# Supply.net
KiCad netlist of a schematic drawn in Altium Designer
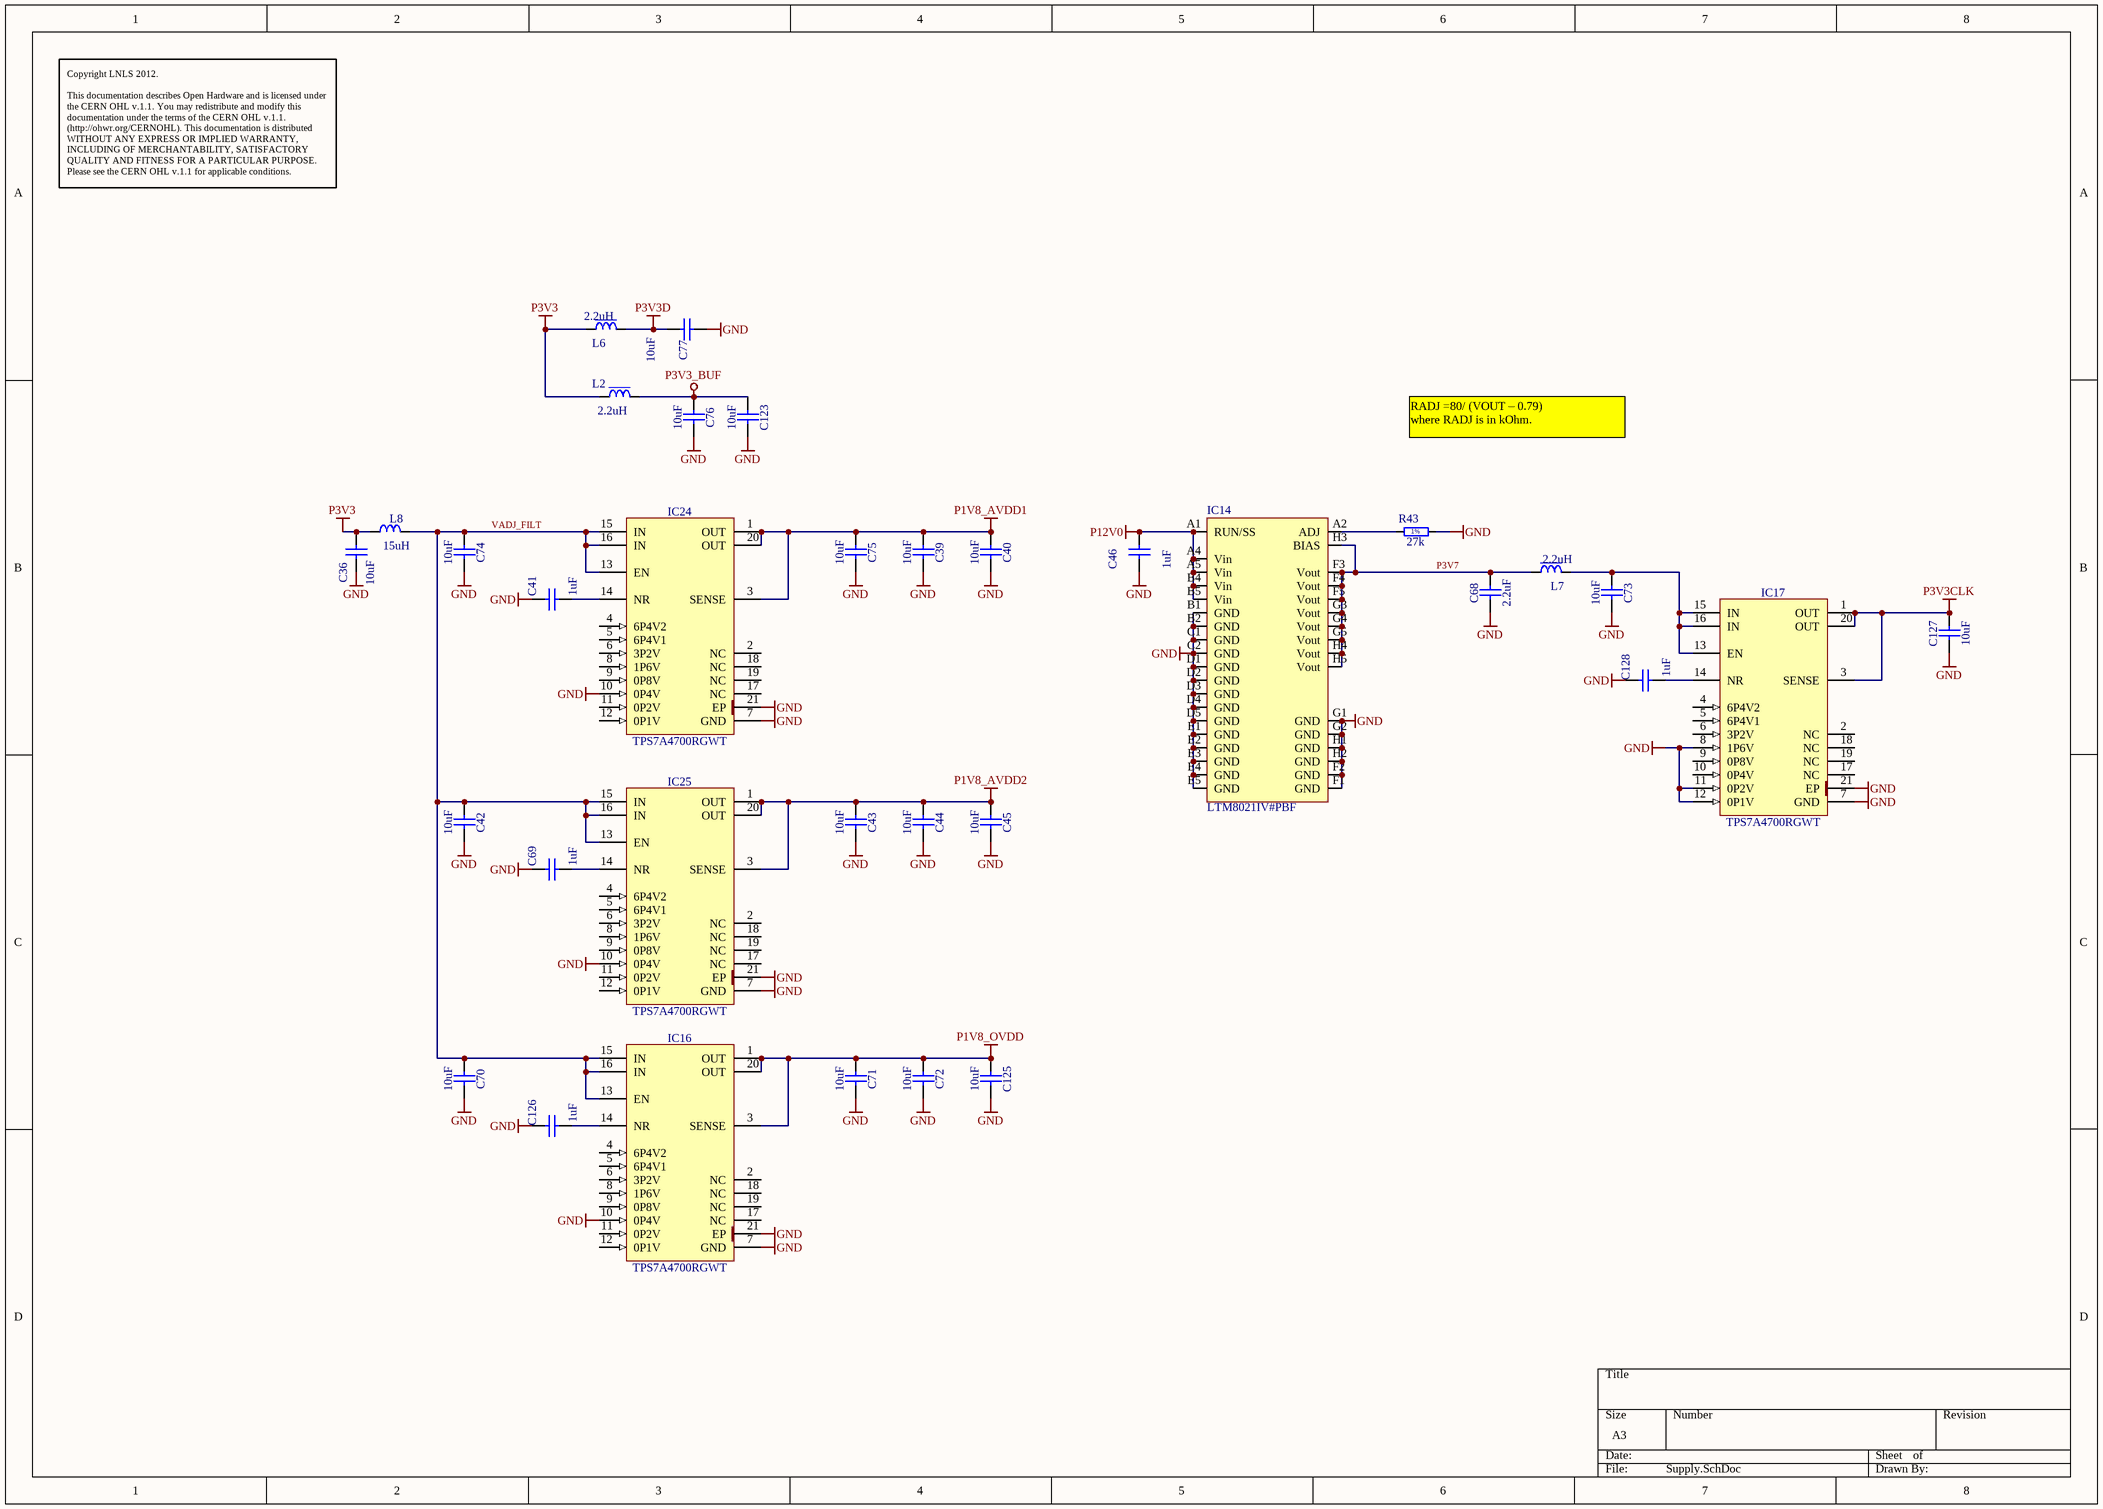
[diagram p0: Supply.SchDoc]

(export (version "E")
  (design (tool "Eeschema 10.0.6"))
  (components
    (comp (ref "C36")
      (value "10uF")
      (footprint "CAPC2012X135N")
      (description "Non-polarised capacitor")
      (fields
        (field (name "PART NUMBER") "CC0805_10UF_16V_10%_X5R")
        (field (name "VOLTAGE") "16V")
        (field (name "AUTHOR") "CERN DEM JLC")
      )
      (libsource (lib "Capacitors") (part "Capacitor - non polarized"))
    )
    (comp (ref "C39")
      (value "10uF")
      (footprint "CAPC2012X135N")
      (description "Non-polarised capacitor")
      (fields
        (field (name "PART NUMBER") "CC0805_10UF_16V_10%_X5R")
        (field (name "VOLTAGE") "16V")
        (field (name "AUTHOR") "CERN DEM JLC")
      )
      (libsource (lib "Capacitors") (part "Capacitor - non polarized"))
    )
    (comp (ref "C40")
      (value "10uF")
      (footprint "CAPC2012X135N")
      (description "Non-polarised capacitor")
      (fields
        (field (name "PART NUMBER") "CC0805_10UF_16V_10%_X5R")
        (field (name "VOLTAGE") "16V")
        (field (name "AUTHOR") "CERN DEM JLC")
      )
      (libsource (lib "Capacitors") (part "Capacitor - non polarized"))
    )
    (comp (ref "C41")
      (value "1uF")
      (footprint "CAPC1608X87N")
      (description "Non-polarised capacitor")
      (fields
        (field (name "PART NUMBER") "CC0603_1UF_16V_10%_X7R")
        (field (name "VOLTAGE") "16V")
        (field (name "AUTHOR") "CERN DEM JLC")
      )
      (libsource (lib "Capacitors") (part "Capacitor - non polarized"))
    )
    (comp (ref "C42")
      (value "10uF")
      (footprint "CAPC2012X135N")
      (description "Non-polarised capacitor")
      (fields
        (field (name "PART NUMBER") "CC0805_10UF_16V_10%_X5R")
        (field (name "VOLTAGE") "16V")
        (field (name "AUTHOR") "CERN DEM JLC")
      )
      (libsource (lib "Capacitors") (part "Capacitor - non polarized"))
    )
    (comp (ref "C43")
      (value "10uF")
      (footprint "CAPC2012X135N")
      (description "Non-polarised capacitor")
      (fields
        (field (name "PART NUMBER") "CC0805_10UF_16V_10%_X5R")
        (field (name "VOLTAGE") "16V")
        (field (name "AUTHOR") "CERN DEM JLC")
      )
      (libsource (lib "Capacitors") (part "Capacitor - non polarized"))
    )
    (comp (ref "C44")
      (value "10uF")
      (footprint "CAPC2012X135N")
      (description "Non-polarised capacitor")
      (fields
        (field (name "PART NUMBER") "CC0805_10UF_16V_10%_X5R")
        (field (name "VOLTAGE") "16V")
        (field (name "AUTHOR") "CERN DEM JLC")
      )
      (libsource (lib "Capacitors") (part "Capacitor - non polarized"))
    )
    (comp (ref "C45")
      (value "10uF")
      (footprint "CAPC2012X135N")
      (description "Non-polarised capacitor")
      (fields
        (field (name "PART NUMBER") "CC0805_10UF_16V_10%_X5R")
        (field (name "VOLTAGE") "16V")
        (field (name "AUTHOR") "CERN DEM JLC")
      )
      (libsource (lib "Capacitors") (part "Capacitor - non polarized"))
    )
    (comp (ref "C46")
      (value "1uF")
      (footprint "CAPC1608X87N")
      (description "Non-polarised capacitor")
      (fields
        (field (name "PART NUMBER") "CC0603_1UF_16V_10%_X7R")
        (field (name "VOLTAGE") "16V")
        (field (name "AUTHOR") "CERN DEM JLC")
      )
      (libsource (lib "Capacitors") (part "Capacitor - non polarized"))
    )
    (comp (ref "C68")
      (value "2.2uF")
      (footprint "CAPC2012X135N")
      (description "Non-polarised capacitor")
      (fields
        (field (name "PART NUMBER") "CC0805_2.2UF_16V_10%_X7R")
        (field (name "VOLTAGE") "16V")
        (field (name "AUTHOR") "CERN DEM JLC")
      )
      (libsource (lib "Capacitors") (part "Capacitor - non polarized"))
    )
    (comp (ref "C69")
      (value "1uF")
      (footprint "CAPC1608X87N")
      (description "Non-polarised capacitor")
      (fields
        (field (name "PART NUMBER") "CC0603_1UF_16V_10%_X7R")
        (field (name "VOLTAGE") "16V")
        (field (name "AUTHOR") "CERN DEM JLC")
      )
      (libsource (lib "Capacitors") (part "Capacitor - non polarized"))
    )
    (comp (ref "C70")
      (value "10uF")
      (footprint "CAPC2012X135N")
      (description "Non-polarised capacitor")
      (fields
        (field (name "PART NUMBER") "CC0805_10UF_16V_10%_X5R")
        (field (name "VOLTAGE") "16V")
        (field (name "AUTHOR") "CERN DEM JLC")
      )
      (libsource (lib "Capacitors") (part "Capacitor - non polarized"))
    )
    (comp (ref "C71")
      (value "10uF")
      (footprint "CAPC2012X135N")
      (description "Non-polarised capacitor")
      (fields
        (field (name "PART NUMBER") "CC0805_10UF_16V_10%_X5R")
        (field (name "VOLTAGE") "16V")
        (field (name "AUTHOR") "CERN DEM JLC")
      )
      (libsource (lib "Capacitors") (part "Capacitor - non polarized"))
    )
    (comp (ref "C72")
      (value "10uF")
      (footprint "CAPC2012X135N")
      (description "Non-polarised capacitor")
      (fields
        (field (name "PART NUMBER") "CC0805_10UF_16V_10%_X5R")
        (field (name "VOLTAGE") "16V")
        (field (name "AUTHOR") "CERN DEM JLC")
      )
      (libsource (lib "Capacitors") (part "Capacitor - non polarized"))
    )
    (comp (ref "C73")
      (value "10uF")
      (footprint "CAPC2012X135N")
      (description "Non-polarised capacitor")
      (fields
        (field (name "PART NUMBER") "CC0805_10UF_16V_10%_X5R")
        (field (name "VOLTAGE") "16V")
        (field (name "AUTHOR") "CERN DEM JLC")
      )
      (libsource (lib "Capacitors") (part "Capacitor - non polarized"))
    )
    (comp (ref "C74")
      (value "10uF")
      (footprint "CAPC2012X135N")
      (description "Non-polarised capacitor")
      (fields
        (field (name "PART NUMBER") "CC0805_10UF_16V_10%_X5R")
        (field (name "VOLTAGE") "16V")
        (field (name "AUTHOR") "CERN DEM JLC")
      )
      (libsource (lib "Capacitors") (part "Capacitor - non polarized"))
    )
    (comp (ref "C75")
      (value "10uF")
      (footprint "CAPC2012X135N")
      (description "Non-polarised capacitor")
      (fields
        (field (name "PART NUMBER") "CC0805_10UF_16V_10%_X5R")
        (field (name "VOLTAGE") "16V")
        (field (name "AUTHOR") "CERN DEM JLC")
      )
      (libsource (lib "Capacitors") (part "Capacitor - non polarized"))
    )
    (comp (ref "C76")
      (value "10uF")
      (footprint "CAPC2012X135N")
      (description "Non-polarised capacitor")
      (fields
        (field (name "PART NUMBER") "CC0805_10UF_16V_10%_X5R")
        (field (name "VOLTAGE") "16V")
        (field (name "AUTHOR") "CERN DEM JLC")
      )
      (libsource (lib "Capacitors") (part "Capacitor - non polarized"))
    )
    (comp (ref "C77")
      (value "10uF")
      (footprint "CAPC2012X135N")
      (description "Non-polarised capacitor")
      (fields
        (field (name "PART NUMBER") "CC0805_10UF_16V_10%_X5R")
        (field (name "VOLTAGE") "16V")
        (field (name "AUTHOR") "CERN DEM JLC")
      )
      (libsource (lib "Capacitors") (part "Capacitor - non polarized"))
    )
    (comp (ref "C123")
      (value "10uF")
      (footprint "CAPC2012X135N")
      (description "Non-polarised capacitor")
      (fields
        (field (name "PART NUMBER") "CC0805_10UF_16V_10%_X5R")
        (field (name "VOLTAGE") "16V")
        (field (name "AUTHOR") "CERN DEM JLC")
      )
      (libsource (lib "Capacitors") (part "Capacitor - non polarized"))
    )
    (comp (ref "C125")
      (value "10uF")
      (footprint "CAPC2012X135N")
      (description "Non-polarised capacitor")
      (fields
        (field (name "PART NUMBER") "CC0805_10UF_16V_10%_X5R")
        (field (name "VOLTAGE") "16V")
        (field (name "AUTHOR") "CERN DEM JLC")
      )
      (libsource (lib "Capacitors") (part "Capacitor - non polarized"))
    )
    (comp (ref "C126")
      (value "1uF")
      (footprint "CAPC1608X87N")
      (description "Non-polarised capacitor")
      (fields
        (field (name "PART NUMBER") "CC0603_1UF_16V_10%_X7R")
        (field (name "VOLTAGE") "16V")
        (field (name "AUTHOR") "CERN DEM JLC")
      )
      (libsource (lib "Capacitors") (part "Capacitor - non polarized"))
    )
    (comp (ref "C127")
      (value "10uF")
      (footprint "CAPC2012X135N")
      (description "Non-polarised capacitor")
      (fields
        (field (name "PART NUMBER") "CC0805_10UF_16V_10%_X5R")
        (field (name "VOLTAGE") "16V")
        (field (name "AUTHOR") "CERN DEM JLC")
      )
      (libsource (lib "Capacitors") (part "Capacitor - non polarized"))
    )
    (comp (ref "C128")
      (value "1uF")
      (footprint "CAPC1608X87N")
      (description "Non-polarised capacitor")
      (fields
        (field (name "PART NUMBER") "CC0603_1UF_16V_10%_X7R")
        (field (name "VOLTAGE") "16V")
        (field (name "AUTHOR") "CERN DEM JLC")
      )
      (libsource (lib "Capacitors") (part "Capacitor - non polarized"))
    )
    (comp (ref "IC14")
      (value "LTM8021IV#PBF")
      (footprint "LGA35S127P5X8")
      (description "36VIN, 500mA  Step-Down DC/DC Module")
      (fields (field (name "MANUFACTURER") "LINEAR TECHNOLOGY") (field (name "AUTHOR") "LNLS DIG GBMB"))
      (libsource (lib "ICs And Semiconductors") (part "DCDC_LINEAR_LTM8021"))
    )
    (comp (ref "IC16")
      (value "TPS7A4700RGWT")
      (footprint "QFN65P500X500X100-21N-S325")
      (description "Low Noise (3uVrms), 1A, High Voltage Low-Dropout Linear Regulator")
      (fields (field (name "MANUFACTURER") "TEXAS INSTRUMENTS") (field (name "AUTHOR") "CERN DEM JLC"))
      (libsource (lib "ICs And Semiconductors") (part "TPS7A4700RGW"))
    )
    (comp (ref "IC17")
      (value "TPS7A4700RGWT")
      (footprint "QFN65P500X500X100-21N-S325")
      (description "Low Noise (3uVrms), 1A, High Voltage Low-Dropout Linear Regulator")
      (fields (field (name "MANUFACTURER") "TEXAS INSTRUMENTS") (field (name "AUTHOR") "CERN DEM JLC"))
      (libsource (lib "ICs And Semiconductors") (part "TPS7A4700RGW"))
    )
    (comp (ref "IC24")
      (value "TPS7A4700RGWT")
      (footprint "QFN65P500X500X100-21N-S325")
      (description "Low Noise (3uVrms), 1A, High Voltage Low-Dropout Linear Regulator")
      (fields (field (name "MANUFACTURER") "TEXAS INSTRUMENTS") (field (name "AUTHOR") "CERN DEM JLC"))
      (libsource (lib "ICs And Semiconductors") (part "TPS7A4700RGW"))
    )
    (comp (ref "IC25")
      (value "TPS7A4700RGWT")
      (footprint "QFN65P500X500X100-21N-S325")
      (description "Low Noise (3uVrms), 1A, High Voltage Low-Dropout Linear Regulator")
      (fields (field (name "MANUFACTURER") "TEXAS INSTRUMENTS") (field (name "AUTHOR") "CERN DEM JLC"))
      (libsource (lib "ICs And Semiconductors") (part "TPS7A4700RGW"))
    )
    (comp (ref "L2")
      (value "2.2uH")
      (footprint "IND_PANASONIC_ELLVGG")
      (description "Inductor With Core")
      (fields
        (field (name "PART NUMBER") "IND_2.2UH_30%_PANASONIC_ELLVGG2R2N")
        (field (name "POWER") "1.4A")
        (field (name "AUTHOR") "LNLS DIG GBMB")
      )
      (libsource (lib "Inductors & Transformers") (part "Inductor With Magnetic core"))
    )
    (comp (ref "L6")
      (value "2.2uH")
      (footprint "IND_PANASONIC_ELLVGG")
      (description "Inductor With Core")
      (fields
        (field (name "PART NUMBER") "IND_2.2UH_30%_PANASONIC_ELLVGG2R2N")
        (field (name "POWER") "1.4A")
        (field (name "AUTHOR") "LNLS DIG GBMB")
      )
      (libsource (lib "Inductors & Transformers") (part "Inductor With Magnetic core"))
    )
    (comp (ref "L7")
      (value "2.2uH")
      (footprint "IND_PANASONIC_ELLVGG")
      (description "Inductor With Core")
      (fields
        (field (name "PART NUMBER") "IND_2.2UH_30%_PANASONIC_ELLVGG2R2N")
        (field (name "POWER") "1.4A")
        (field (name "AUTHOR") "LNLS DIG GBMB")
      )
      (libsource (lib "Inductors & Transformers") (part "Inductor With Magnetic core"))
    )
    (comp (ref "L8")
      (value "15uH")
      (footprint "IND_TDK_VLCF4020-1")
      (description "Inductor")
      (fields
        (field (name "PART NUMBER") "IND_15UH_20%_TDK_VLCF4020-1")
        (field (name "POWER") "0.68A")
        (field (name "AUTHOR") "LNLS DIG GBMB")
      )
      (libsource (lib "Inductors & Transformers") (part "Inductor"))
    )
    (comp (ref "R43")
      (value "27k")
      (footprint "RESC1608X55N")
      (description "Resistor - 1%")
      (fields
        (field (name "PART NUMBER") "R0603_27K_1%_0.1W_100PPM")
        (field (name "POWER") "0.1W")
        (field (name "AUTHOR") "CERN DEM JLC")
      )
      (libsource (lib "Resistors") (part "Resistor - 1%"))
    )
  )
  (nets
    (net (code "1") (name "/P3V7") (class "Default")
      (node (ref "C68") (pin "2") (pinfunction "2_2") (pintype "passive"))
      (node (ref "IC14") (pin "F3") (pinfunction "Vout_F3") (pintype "passive"))
      (node (ref "IC14") (pin "F4") (pinfunction "Vout_F4") (pintype "passive"))
      (node (ref "IC14") (pin "F5") (pinfunction "Vout_F5") (pintype "passive"))
      (node (ref "IC14") (pin "G3") (pinfunction "Vout_G3") (pintype "passive"))
      (node (ref "IC14") (pin "G4") (pinfunction "Vout_G4") (pintype "passive"))
      (node (ref "IC14") (pin "G5") (pinfunction "Vout_G5") (pintype "passive"))
      (node (ref "IC14") (pin "H3") (pinfunction "BIAS_H3") (pintype "power_in"))
      (node (ref "IC14") (pin "H4") (pinfunction "Vout_H4") (pintype "passive"))
      (node (ref "IC14") (pin "H5") (pinfunction "Vout_H5") (pintype "passive"))
      (node (ref "L7") (pin "1") (pinfunction "1_1") (pintype "passive"))
    )
    (net (code "2") (name "/VADJ_FILT") (class "Default")
      (node (ref "C42") (pin "1") (pinfunction "1_1") (pintype "passive"))
      (node (ref "C70") (pin "1") (pinfunction "1_1") (pintype "passive"))
      (node (ref "C74") (pin "1") (pinfunction "1_1") (pintype "passive"))
      (node (ref "IC16") (pin "13") (pinfunction "EN_13") (pintype "passive"))
      (node (ref "IC16") (pin "15") (pinfunction "IN_15") (pintype "power_in"))
      (node (ref "IC16") (pin "16") (pinfunction "IN_16") (pintype "power_in"))
      (node (ref "IC24") (pin "13") (pinfunction "EN_13") (pintype "passive"))
      (node (ref "IC24") (pin "15") (pinfunction "IN_15") (pintype "power_in"))
      (node (ref "IC24") (pin "16") (pinfunction "IN_16") (pintype "power_in"))
      (node (ref "IC25") (pin "13") (pinfunction "EN_13") (pintype "passive"))
      (node (ref "IC25") (pin "15") (pinfunction "IN_15") (pintype "power_in"))
      (node (ref "IC25") (pin "16") (pinfunction "IN_16") (pintype "power_in"))
      (node (ref "L8") (pin "2") (pinfunction "2_2") (pintype "passive"))
    )
    (net (code "3") (name "GND") (class "Default")
      (node (ref "C123") (pin "2") (pinfunction "2_2") (pintype "passive"))
      (node (ref "C125") (pin "2") (pinfunction "2_2") (pintype "passive"))
      (node (ref "C126") (pin "2") (pinfunction "2_2") (pintype "passive"))
      (node (ref "C127") (pin "1") (pinfunction "1_1") (pintype "passive"))
      (node (ref "C128") (pin "2") (pinfunction "2_2") (pintype "passive"))
      (node (ref "C36") (pin "2") (pinfunction "2_2") (pintype "passive"))
      (node (ref "C39") (pin "2") (pinfunction "2_2") (pintype "passive"))
      (node (ref "C40") (pin "2") (pinfunction "2_2") (pintype "passive"))
      (node (ref "C41") (pin "2") (pinfunction "2_2") (pintype "passive"))
      (node (ref "C42") (pin "2") (pinfunction "2_2") (pintype "passive"))
      (node (ref "C43") (pin "2") (pinfunction "2_2") (pintype "passive"))
      (node (ref "C44") (pin "2") (pinfunction "2_2") (pintype "passive"))
      (node (ref "C45") (pin "2") (pinfunction "2_2") (pintype "passive"))
      (node (ref "C46") (pin "2") (pinfunction "2_2") (pintype "passive"))
      (node (ref "C68") (pin "1") (pinfunction "1_1") (pintype "passive"))
      (node (ref "C69") (pin "2") (pinfunction "2_2") (pintype "passive"))
      (node (ref "C70") (pin "2") (pinfunction "2_2") (pintype "passive"))
      (node (ref "C71") (pin "2") (pinfunction "2_2") (pintype "passive"))
      (node (ref "C72") (pin "2") (pinfunction "2_2") (pintype "passive"))
      (node (ref "C73") (pin "2") (pinfunction "2_2") (pintype "passive"))
      (node (ref "C74") (pin "2") (pinfunction "2_2") (pintype "passive"))
      (node (ref "C75") (pin "2") (pinfunction "2_2") (pintype "passive"))
      (node (ref "C76") (pin "2") (pinfunction "2_2") (pintype "passive"))
      (node (ref "C77") (pin "2") (pinfunction "2_2") (pintype "passive"))
      (node (ref "IC14") (pin "B1") (pinfunction "GND_B1") (pintype "power_in"))
      (node (ref "IC14") (pin "B2") (pinfunction "GND_B2") (pintype "power_in"))
      (node (ref "IC14") (pin "C1") (pinfunction "GND_C1") (pintype "power_in"))
      (node (ref "IC14") (pin "C2") (pinfunction "GND_C2") (pintype "power_in"))
      (node (ref "IC14") (pin "D1") (pinfunction "GND_D1") (pintype "power_in"))
      (node (ref "IC14") (pin "D2") (pinfunction "GND_D2") (pintype "power_in"))
      (node (ref "IC14") (pin "D3") (pinfunction "GND_D3") (pintype "power_in"))
      (node (ref "IC14") (pin "D4") (pinfunction "GND_D4") (pintype "power_in"))
      (node (ref "IC14") (pin "D5") (pinfunction "GND_D5") (pintype "power_in"))
      (node (ref "IC14") (pin "E1") (pinfunction "GND_E1") (pintype "power_in"))
      (node (ref "IC14") (pin "E2") (pinfunction "GND_E2") (pintype "power_in"))
      (node (ref "IC14") (pin "E3") (pinfunction "GND_E3") (pintype "power_in"))
      (node (ref "IC14") (pin "E4") (pinfunction "GND_E4") (pintype "power_in"))
      (node (ref "IC14") (pin "E5") (pinfunction "GND_E5") (pintype "power_in"))
      (node (ref "IC14") (pin "F1") (pinfunction "GND_F1") (pintype "power_in"))
      (node (ref "IC14") (pin "F2") (pinfunction "GND_F2") (pintype "power_in"))
      (node (ref "IC14") (pin "G1") (pinfunction "GND_G1") (pintype "power_in"))
      (node (ref "IC14") (pin "G2") (pinfunction "GND_G2") (pintype "power_in"))
      (node (ref "IC14") (pin "H1") (pinfunction "GND_H1") (pintype "power_in"))
      (node (ref "IC14") (pin "H2") (pinfunction "GND_H2") (pintype "power_in"))
      (node (ref "IC16") (pin "10") (pinfunction "0P4V_10") (pintype "input"))
      (node (ref "IC16") (pin "21") (pinfunction "EP_21") (pintype "power_in"))
      (node (ref "IC16") (pin "7") (pinfunction "GND_7") (pintype "power_in"))
      (node (ref "IC17") (pin "11") (pinfunction "0P2V_11") (pintype "input"))
      (node (ref "IC17") (pin "12") (pinfunction "0P1V_12") (pintype "input"))
      (node (ref "IC17") (pin "21") (pinfunction "EP_21") (pintype "power_in"))
      (node (ref "IC17") (pin "7") (pinfunction "GND_7") (pintype "power_in"))
      (node (ref "IC17") (pin "8") (pinfunction "1P6V_8") (pintype "input"))
      (node (ref "IC24") (pin "10") (pinfunction "0P4V_10") (pintype "input"))
      (node (ref "IC24") (pin "21") (pinfunction "EP_21") (pintype "power_in"))
      (node (ref "IC24") (pin "7") (pinfunction "GND_7") (pintype "power_in"))
      (node (ref "IC25") (pin "10") (pinfunction "0P4V_10") (pintype "input"))
      (node (ref "IC25") (pin "21") (pinfunction "EP_21") (pintype "power_in"))
      (node (ref "IC25") (pin "7") (pinfunction "GND_7") (pintype "power_in"))
      (node (ref "R43") (pin "2") (pinfunction "2_2") (pintype "passive"))
    )
    (net (code "4") (name "Net-(IC14-ADJ)") (class "Default")
      (node (ref "IC14") (pin "A2") (pinfunction "ADJ_A2") (pintype "passive"))
      (node (ref "R43") (pin "1") (pinfunction "1_1") (pintype "passive"))
    )
    (net (code "5") (name "Net-(IC16-NR)") (class "Default")
      (node (ref "C126") (pin "1") (pinfunction "1_1") (pintype "passive"))
      (node (ref "IC16") (pin "14") (pinfunction "NR_14") (pintype "passive"))
    )
    (net (code "6") (name "Net-(IC17-EN)") (class "Default")
      (node (ref "C73") (pin "1") (pinfunction "1_1") (pintype "passive"))
      (node (ref "IC17") (pin "13") (pinfunction "EN_13") (pintype "passive"))
      (node (ref "IC17") (pin "15") (pinfunction "IN_15") (pintype "power_in"))
      (node (ref "IC17") (pin "16") (pinfunction "IN_16") (pintype "power_in"))
      (node (ref "L7") (pin "2") (pinfunction "2_2") (pintype "passive"))
    )
    (net (code "7") (name "Net-(IC17-NR)") (class "Default")
      (node (ref "C128") (pin "1") (pinfunction "1_1") (pintype "passive"))
      (node (ref "IC17") (pin "14") (pinfunction "NR_14") (pintype "passive"))
    )
    (net (code "8") (name "Net-(IC24-NR)") (class "Default")
      (node (ref "C41") (pin "1") (pinfunction "1_1") (pintype "passive"))
      (node (ref "IC24") (pin "14") (pinfunction "NR_14") (pintype "passive"))
    )
    (net (code "9") (name "Net-(IC25-NR)") (class "Default")
      (node (ref "C69") (pin "1") (pinfunction "1_1") (pintype "passive"))
      (node (ref "IC25") (pin "14") (pinfunction "NR_14") (pintype "passive"))
    )
    (net (code "10") (name "P1V8_AVDD1") (class "Default")
      (node (ref "C39") (pin "1") (pinfunction "1_1") (pintype "passive"))
      (node (ref "C40") (pin "1") (pinfunction "1_1") (pintype "passive"))
      (node (ref "C75") (pin "1") (pinfunction "1_1") (pintype "passive"))
      (node (ref "IC24") (pin "1") (pinfunction "OUT_1") (pintype "power_in"))
      (node (ref "IC24") (pin "20") (pinfunction "OUT_20") (pintype "power_in"))
      (node (ref "IC24") (pin "3") (pinfunction "SENSE_3") (pintype "passive"))
    )
    (net (code "11") (name "P1V8_AVDD2") (class "Default")
      (node (ref "C43") (pin "1") (pinfunction "1_1") (pintype "passive"))
      (node (ref "C44") (pin "1") (pinfunction "1_1") (pintype "passive"))
      (node (ref "C45") (pin "1") (pinfunction "1_1") (pintype "passive"))
      (node (ref "IC25") (pin "1") (pinfunction "OUT_1") (pintype "power_in"))
      (node (ref "IC25") (pin "20") (pinfunction "OUT_20") (pintype "power_in"))
      (node (ref "IC25") (pin "3") (pinfunction "SENSE_3") (pintype "passive"))
    )
    (net (code "12") (name "P1V8_OVDD") (class "Default")
      (node (ref "C125") (pin "1") (pinfunction "1_1") (pintype "passive"))
      (node (ref "C71") (pin "1") (pinfunction "1_1") (pintype "passive"))
      (node (ref "C72") (pin "1") (pinfunction "1_1") (pintype "passive"))
      (node (ref "IC16") (pin "1") (pinfunction "OUT_1") (pintype "power_in"))
      (node (ref "IC16") (pin "20") (pinfunction "OUT_20") (pintype "power_in"))
      (node (ref "IC16") (pin "3") (pinfunction "SENSE_3") (pintype "passive"))
    )
    (net (code "13") (name "P3V3") (class "Default")
      (node (ref "C36") (pin "1") (pinfunction "1_1") (pintype "passive"))
      (node (ref "L2") (pin "1") (pinfunction "1_1") (pintype "passive"))
      (node (ref "L6") (pin "1") (pinfunction "1_1") (pintype "passive"))
      (node (ref "L8") (pin "1") (pinfunction "1_1") (pintype "passive"))
    )
    (net (code "14") (name "P3V3CLK") (class "Default")
      (node (ref "C127") (pin "2") (pinfunction "2_2") (pintype "passive"))
      (node (ref "IC17") (pin "1") (pinfunction "OUT_1") (pintype "power_in"))
      (node (ref "IC17") (pin "20") (pinfunction "OUT_20") (pintype "power_in"))
      (node (ref "IC17") (pin "3") (pinfunction "SENSE_3") (pintype "passive"))
    )
    (net (code "15") (name "P3V3D") (class "Default")
      (node (ref "C77") (pin "1") (pinfunction "1_1") (pintype "passive"))
      (node (ref "L6") (pin "2") (pinfunction "2_2") (pintype "passive"))
    )
    (net (code "16") (name "P3V3_BUF") (class "Default")
      (node (ref "C123") (pin "1") (pinfunction "1_1") (pintype "passive"))
      (node (ref "C76") (pin "1") (pinfunction "1_1") (pintype "passive"))
      (node (ref "L2") (pin "2") (pinfunction "2_2") (pintype "passive"))
    )
    (net (code "17") (name "P12V0") (class "Default")
      (node (ref "C46") (pin "1") (pinfunction "1_1") (pintype "passive"))
      (node (ref "IC14") (pin "A1") (pinfunction "RUN/SS_A1") (pintype "passive"))
      (node (ref "IC14") (pin "A4") (pinfunction "Vin_A4") (pintype "power_in"))
      (node (ref "IC14") (pin "A5") (pinfunction "Vin_A5") (pintype "power_in"))
      (node (ref "IC14") (pin "B4") (pinfunction "Vin_B4") (pintype "power_in"))
      (node (ref "IC14") (pin "B5") (pinfunction "Vin_B5") (pintype "power_in"))
    )
    (net (code "18") (name "unconnected-(IC16-0P1V-Pad12)") (class "Default")
      (node (ref "IC16") (pin "12") (pinfunction "0P1V_12") (pintype "input"))
    )
    (net (code "19") (name "unconnected-(IC16-0P2V-Pad11)") (class "Default")
      (node (ref "IC16") (pin "11") (pinfunction "0P2V_11") (pintype "input"))
    )
    (net (code "20") (name "unconnected-(IC16-0P8V-Pad9)") (class "Default")
      (node (ref "IC16") (pin "9") (pinfunction "0P8V_9") (pintype "input"))
    )
    (net (code "21") (name "unconnected-(IC16-1P6V-Pad8)") (class "Default")
      (node (ref "IC16") (pin "8") (pinfunction "1P6V_8") (pintype "input"))
    )
    (net (code "22") (name "unconnected-(IC16-3P2V-Pad6)") (class "Default")
      (node (ref "IC16") (pin "6") (pinfunction "3P2V_6") (pintype "input"))
    )
    (net (code "23") (name "unconnected-(IC16-6P4V1-Pad5)") (class "Default")
      (node (ref "IC16") (pin "5") (pinfunction "6P4V1_5") (pintype "input"))
    )
    (net (code "24") (name "unconnected-(IC16-6P4V2-Pad4)") (class "Default")
      (node (ref "IC16") (pin "4") (pinfunction "6P4V2_4") (pintype "input"))
    )
    (net (code "25") (name "unconnected-(IC16-NC-Pad2)") (class "Default")
      (node (ref "IC16") (pin "2") (pinfunction "NC_2") (pintype "passive"))
    )
    (net (code "26") (name "unconnected-(IC16-NC-Pad17)") (class "Default")
      (node (ref "IC16") (pin "17") (pinfunction "NC_17") (pintype "passive"))
    )
    (net (code "27") (name "unconnected-(IC16-NC-Pad18)") (class "Default")
      (node (ref "IC16") (pin "18") (pinfunction "NC_18") (pintype "passive"))
    )
    (net (code "28") (name "unconnected-(IC16-NC-Pad19)") (class "Default")
      (node (ref "IC16") (pin "19") (pinfunction "NC_19") (pintype "passive"))
    )
    (net (code "29") (name "unconnected-(IC17-0P4V-Pad10)") (class "Default")
      (node (ref "IC17") (pin "10") (pinfunction "0P4V_10") (pintype "input"))
    )
    (net (code "30") (name "unconnected-(IC17-0P8V-Pad9)") (class "Default")
      (node (ref "IC17") (pin "9") (pinfunction "0P8V_9") (pintype "input"))
    )
    (net (code "31") (name "unconnected-(IC17-3P2V-Pad6)") (class "Default")
      (node (ref "IC17") (pin "6") (pinfunction "3P2V_6") (pintype "input"))
    )
    (net (code "32") (name "unconnected-(IC17-6P4V1-Pad5)") (class "Default")
      (node (ref "IC17") (pin "5") (pinfunction "6P4V1_5") (pintype "input"))
    )
    (net (code "33") (name "unconnected-(IC17-6P4V2-Pad4)") (class "Default")
      (node (ref "IC17") (pin "4") (pinfunction "6P4V2_4") (pintype "input"))
    )
    (net (code "34") (name "unconnected-(IC17-NC-Pad2)") (class "Default")
      (node (ref "IC17") (pin "2") (pinfunction "NC_2") (pintype "passive"))
    )
    (net (code "35") (name "unconnected-(IC17-NC-Pad17)") (class "Default")
      (node (ref "IC17") (pin "17") (pinfunction "NC_17") (pintype "passive"))
    )
    (net (code "36") (name "unconnected-(IC17-NC-Pad18)") (class "Default")
      (node (ref "IC17") (pin "18") (pinfunction "NC_18") (pintype "passive"))
    )
    (net (code "37") (name "unconnected-(IC17-NC-Pad19)") (class "Default")
      (node (ref "IC17") (pin "19") (pinfunction "NC_19") (pintype "passive"))
    )
    (net (code "38") (name "unconnected-(IC24-0P1V-Pad12)") (class "Default")
      (node (ref "IC24") (pin "12") (pinfunction "0P1V_12") (pintype "input"))
    )
    (net (code "39") (name "unconnected-(IC24-0P2V-Pad11)") (class "Default")
      (node (ref "IC24") (pin "11") (pinfunction "0P2V_11") (pintype "input"))
    )
    (net (code "40") (name "unconnected-(IC24-0P8V-Pad9)") (class "Default")
      (node (ref "IC24") (pin "9") (pinfunction "0P8V_9") (pintype "input"))
    )
    (net (code "41") (name "unconnected-(IC24-1P6V-Pad8)") (class "Default")
      (node (ref "IC24") (pin "8") (pinfunction "1P6V_8") (pintype "input"))
    )
    (net (code "42") (name "unconnected-(IC24-3P2V-Pad6)") (class "Default")
      (node (ref "IC24") (pin "6") (pinfunction "3P2V_6") (pintype "input"))
    )
    (net (code "43") (name "unconnected-(IC24-6P4V1-Pad5)") (class "Default")
      (node (ref "IC24") (pin "5") (pinfunction "6P4V1_5") (pintype "input"))
    )
    (net (code "44") (name "unconnected-(IC24-6P4V2-Pad4)") (class "Default")
      (node (ref "IC24") (pin "4") (pinfunction "6P4V2_4") (pintype "input"))
    )
    (net (code "45") (name "unconnected-(IC24-NC-Pad2)") (class "Default")
      (node (ref "IC24") (pin "2") (pinfunction "NC_2") (pintype "passive"))
    )
    (net (code "46") (name "unconnected-(IC24-NC-Pad17)") (class "Default")
      (node (ref "IC24") (pin "17") (pinfunction "NC_17") (pintype "passive"))
    )
    (net (code "47") (name "unconnected-(IC24-NC-Pad18)") (class "Default")
      (node (ref "IC24") (pin "18") (pinfunction "NC_18") (pintype "passive"))
    )
    (net (code "48") (name "unconnected-(IC24-NC-Pad19)") (class "Default")
      (node (ref "IC24") (pin "19") (pinfunction "NC_19") (pintype "passive"))
    )
    (net (code "49") (name "unconnected-(IC25-0P1V-Pad12)") (class "Default")
      (node (ref "IC25") (pin "12") (pinfunction "0P1V_12") (pintype "input"))
    )
    (net (code "50") (name "unconnected-(IC25-0P2V-Pad11)") (class "Default")
      (node (ref "IC25") (pin "11") (pinfunction "0P2V_11") (pintype "input"))
    )
    (net (code "51") (name "unconnected-(IC25-0P8V-Pad9)") (class "Default")
      (node (ref "IC25") (pin "9") (pinfunction "0P8V_9") (pintype "input"))
    )
    (net (code "52") (name "unconnected-(IC25-1P6V-Pad8)") (class "Default")
      (node (ref "IC25") (pin "8") (pinfunction "1P6V_8") (pintype "input"))
    )
    (net (code "53") (name "unconnected-(IC25-3P2V-Pad6)") (class "Default")
      (node (ref "IC25") (pin "6") (pinfunction "3P2V_6") (pintype "input"))
    )
    (net (code "54") (name "unconnected-(IC25-6P4V1-Pad5)") (class "Default")
      (node (ref "IC25") (pin "5") (pinfunction "6P4V1_5") (pintype "input"))
    )
    (net (code "55") (name "unconnected-(IC25-6P4V2-Pad4)") (class "Default")
      (node (ref "IC25") (pin "4") (pinfunction "6P4V2_4") (pintype "input"))
    )
    (net (code "56") (name "unconnected-(IC25-NC-Pad2)") (class "Default")
      (node (ref "IC25") (pin "2") (pinfunction "NC_2") (pintype "passive"))
    )
    (net (code "57") (name "unconnected-(IC25-NC-Pad17)") (class "Default")
      (node (ref "IC25") (pin "17") (pinfunction "NC_17") (pintype "passive"))
    )
    (net (code "58") (name "unconnected-(IC25-NC-Pad18)") (class "Default")
      (node (ref "IC25") (pin "18") (pinfunction "NC_18") (pintype "passive"))
    )
    (net (code "59") (name "unconnected-(IC25-NC-Pad19)") (class "Default")
      (node (ref "IC25") (pin "19") (pinfunction "NC_19") (pintype "passive"))
    )
  )
)
